# input_board_proto_rev1.net
KiCad netlist of a schematic drawn in EAGLE
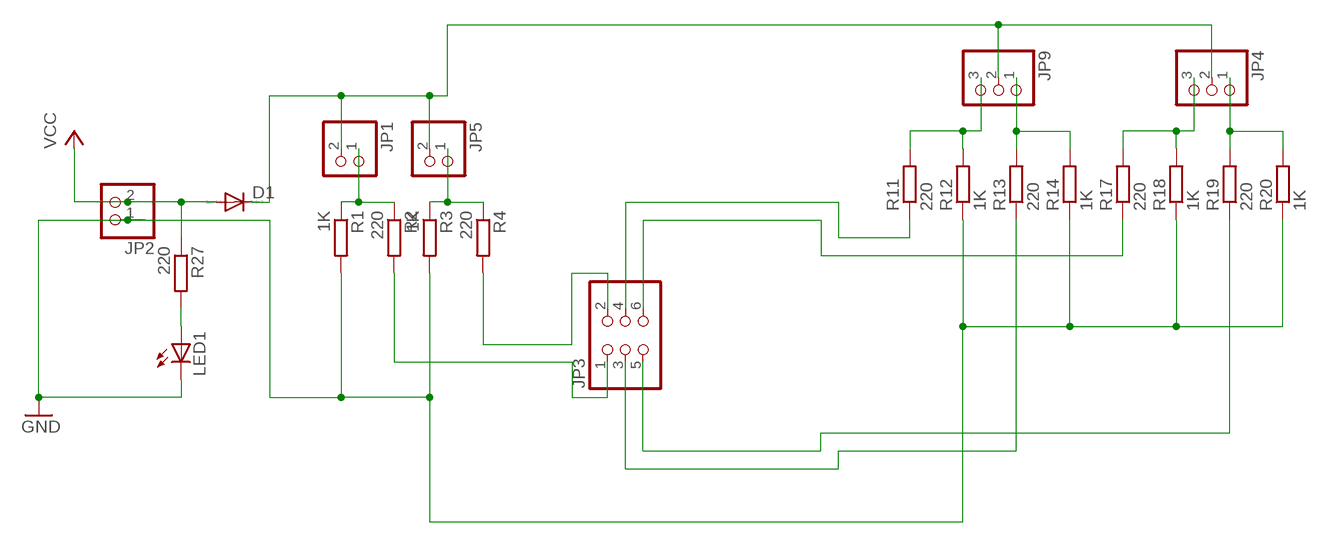
[diagram p0: schematic, sheet 1]

(export (version "E")
  (design (tool "Eeschema 10.0.6"))
  (components
    (comp (ref "D1")
      (value "DIODE-C1702-05")
      (footprint "eagle-import:C1702-05")
      (libsource (lib "eagle-import") (part "DIODE-C1702-05"))
    )
    (comp (ref "JP1")
      (value "PINHD-1X2")
      (footprint "eagle-import:1X02")
      (libsource (lib "eagle-import") (part "PINHD-1X2"))
    )
    (comp (ref "JP2")
      (value "PINHD-1X2")
      (footprint "eagle-import:1X02")
      (libsource (lib "eagle-import") (part "PINHD-1X2"))
    )
    (comp (ref "JP3")
      (value "PINHD-2X3")
      (footprint "eagle-import:2X03")
      (libsource (lib "eagle-import") (part "PINHD-2X3"))
    )
    (comp (ref "JP4")
      (value "PINHD-1X3")
      (footprint "eagle-import:1X03")
      (libsource (lib "eagle-import") (part "PINHD-1X3"))
    )
    (comp (ref "JP5")
      (value "PINHD-1X2")
      (footprint "eagle-import:1X02")
      (libsource (lib "eagle-import") (part "PINHD-1X2"))
    )
    (comp (ref "JP9")
      (value "PINHD-1X3")
      (footprint "eagle-import:1X03")
      (libsource (lib "eagle-import") (part "PINHD-1X3"))
    )
    (comp (ref "LED1")
      (value "LED3MM")
      (footprint "eagle-import:LED3MM")
      (libsource (lib "eagle-import") (part "LED3MM"))
    )
    (comp (ref "R1")
      (value "1K")
      (footprint "eagle-import:0204V")
      (libsource (lib "eagle-import") (part "R-EU_0204/2V"))
    )
    (comp (ref "R2")
      (value "220")
      (footprint "eagle-import:0204V")
      (libsource (lib "eagle-import") (part "R-EU_0204/2V"))
    )
    (comp (ref "R3")
      (value "1K")
      (footprint "eagle-import:0204V")
      (libsource (lib "eagle-import") (part "R-EU_0204/2V"))
    )
    (comp (ref "R4")
      (value "220")
      (footprint "eagle-import:0204V")
      (libsource (lib "eagle-import") (part "R-EU_0204/2V"))
    )
    (comp (ref "R11")
      (value "220")
      (footprint "eagle-import:0204V")
      (libsource (lib "eagle-import") (part "R-EU_0204/2V"))
    )
    (comp (ref "R12")
      (value "1K")
      (footprint "eagle-import:0204V")
      (libsource (lib "eagle-import") (part "R-EU_0204/2V"))
    )
    (comp (ref "R13")
      (value "220")
      (footprint "eagle-import:0204V")
      (libsource (lib "eagle-import") (part "R-EU_0204/2V"))
    )
    (comp (ref "R14")
      (value "1K")
      (footprint "eagle-import:0204V")
      (libsource (lib "eagle-import") (part "R-EU_0204/2V"))
    )
    (comp (ref "R17")
      (value "220")
      (footprint "eagle-import:0204V")
      (libsource (lib "eagle-import") (part "R-EU_0204/2V"))
    )
    (comp (ref "R18")
      (value "1K")
      (footprint "eagle-import:0204V")
      (libsource (lib "eagle-import") (part "R-EU_0204/2V"))
    )
    (comp (ref "R19")
      (value "220")
      (footprint "eagle-import:0204V")
      (libsource (lib "eagle-import") (part "R-EU_0204/2V"))
    )
    (comp (ref "R20")
      (value "1K")
      (footprint "eagle-import:0204V")
      (libsource (lib "eagle-import") (part "R-EU_0204/2V"))
    )
    (comp (ref "R27")
      (value "220")
      (footprint "eagle-import:0204V")
      (libsource (lib "eagle-import") (part "R-EU_0204/2V"))
    )
  )
  (nets
    (net (code "1") (name "GND") (class "Default")
      (node (ref "JP2") (pin "1") (pinfunction "1_1") (pintype "passive"))
      (node (ref "LED1") (pin "K") (pinfunction "C_K") (pintype "passive"))
      (node (ref "R1") (pin "2") (pinfunction "2_2") (pintype "passive"))
      (node (ref "R12") (pin "1") (pinfunction "1_1") (pintype "passive"))
      (node (ref "R14") (pin "1") (pinfunction "1_1") (pintype "passive"))
      (node (ref "R18") (pin "1") (pinfunction "1_1") (pintype "passive"))
      (node (ref "R20") (pin "1") (pinfunction "1_1") (pintype "passive"))
      (node (ref "R3") (pin "2") (pinfunction "2_2") (pintype "passive"))
    )
    (net (code "2") (name "Net-(D1-PadC)") (class "Default")
      (node (ref "D1") (pin "C") (pinfunction "C_C") (pintype "passive"))
      (node (ref "JP1") (pin "2") (pinfunction "2_2") (pintype "passive"))
      (node (ref "JP4") (pin "2") (pinfunction "2_2") (pintype "passive"))
      (node (ref "JP5") (pin "2") (pinfunction "2_2") (pintype "passive"))
      (node (ref "JP9") (pin "2") (pinfunction "2_2") (pintype "passive"))
    )
    (net (code "3") (name "Net-(JP1-Pad1)") (class "Default")
      (node (ref "JP1") (pin "1") (pinfunction "1_1") (pintype "passive"))
      (node (ref "R1") (pin "1") (pinfunction "1_1") (pintype "passive"))
      (node (ref "R2") (pin "1") (pinfunction "1_1") (pintype "passive"))
    )
    (net (code "4") (name "Net-(JP3-Pad1)") (class "Default")
      (node (ref "JP3") (pin "1") (pinfunction "1_1") (pintype "passive"))
      (node (ref "R2") (pin "2") (pinfunction "2_2") (pintype "passive"))
    )
    (net (code "5") (name "Net-(JP3-Pad2)") (class "Default")
      (node (ref "JP3") (pin "2") (pinfunction "2_2") (pintype "passive"))
      (node (ref "R4") (pin "2") (pinfunction "2_2") (pintype "passive"))
    )
    (net (code "6") (name "Net-(JP3-Pad3)") (class "Default")
      (node (ref "JP3") (pin "3") (pinfunction "3_3") (pintype "passive"))
      (node (ref "R13") (pin "1") (pinfunction "1_1") (pintype "passive"))
    )
    (net (code "7") (name "Net-(JP3-Pad4)") (class "Default")
      (node (ref "JP3") (pin "4") (pinfunction "4_4") (pintype "passive"))
      (node (ref "R11") (pin "1") (pinfunction "1_1") (pintype "passive"))
    )
    (net (code "8") (name "Net-(JP3-Pad5)") (class "Default")
      (node (ref "JP3") (pin "5") (pinfunction "5_5") (pintype "passive"))
      (node (ref "R19") (pin "1") (pinfunction "1_1") (pintype "passive"))
    )
    (net (code "9") (name "Net-(JP3-Pad6)") (class "Default")
      (node (ref "JP3") (pin "6") (pinfunction "6_6") (pintype "passive"))
      (node (ref "R17") (pin "1") (pinfunction "1_1") (pintype "passive"))
    )
    (net (code "10") (name "Net-(JP4-Pad1)") (class "Default")
      (node (ref "JP4") (pin "1") (pinfunction "1_1") (pintype "passive"))
      (node (ref "R19") (pin "2") (pinfunction "2_2") (pintype "passive"))
      (node (ref "R20") (pin "2") (pinfunction "2_2") (pintype "passive"))
    )
    (net (code "11") (name "Net-(JP4-Pad3)") (class "Default")
      (node (ref "JP4") (pin "3") (pinfunction "3_3") (pintype "passive"))
      (node (ref "R17") (pin "2") (pinfunction "2_2") (pintype "passive"))
      (node (ref "R18") (pin "2") (pinfunction "2_2") (pintype "passive"))
    )
    (net (code "12") (name "Net-(JP5-Pad1)") (class "Default")
      (node (ref "JP5") (pin "1") (pinfunction "1_1") (pintype "passive"))
      (node (ref "R3") (pin "1") (pinfunction "1_1") (pintype "passive"))
      (node (ref "R4") (pin "1") (pinfunction "1_1") (pintype "passive"))
    )
    (net (code "13") (name "Net-(JP9-Pad1)") (class "Default")
      (node (ref "JP9") (pin "1") (pinfunction "1_1") (pintype "passive"))
      (node (ref "R13") (pin "2") (pinfunction "2_2") (pintype "passive"))
      (node (ref "R14") (pin "2") (pinfunction "2_2") (pintype "passive"))
    )
    (net (code "14") (name "Net-(JP9-Pad3)") (class "Default")
      (node (ref "JP9") (pin "3") (pinfunction "3_3") (pintype "passive"))
      (node (ref "R11") (pin "2") (pinfunction "2_2") (pintype "passive"))
      (node (ref "R12") (pin "2") (pinfunction "2_2") (pintype "passive"))
    )
    (net (code "15") (name "Net-(LED1-PadA)") (class "Default")
      (node (ref "LED1") (pin "A") (pinfunction "A_A") (pintype "passive"))
      (node (ref "R27") (pin "2") (pinfunction "2_2") (pintype "passive"))
    )
    (net (code "16") (name "VCC") (class "Default")
      (node (ref "D1") (pin "A") (pinfunction "A_A") (pintype "passive"))
      (node (ref "JP2") (pin "2") (pinfunction "2_2") (pintype "passive"))
      (node (ref "R27") (pin "1") (pinfunction "1_1") (pintype "passive"))
    )
  )
)
